# esp32programmer.net
KiCad netlist of a schematic drawn in EAGLE
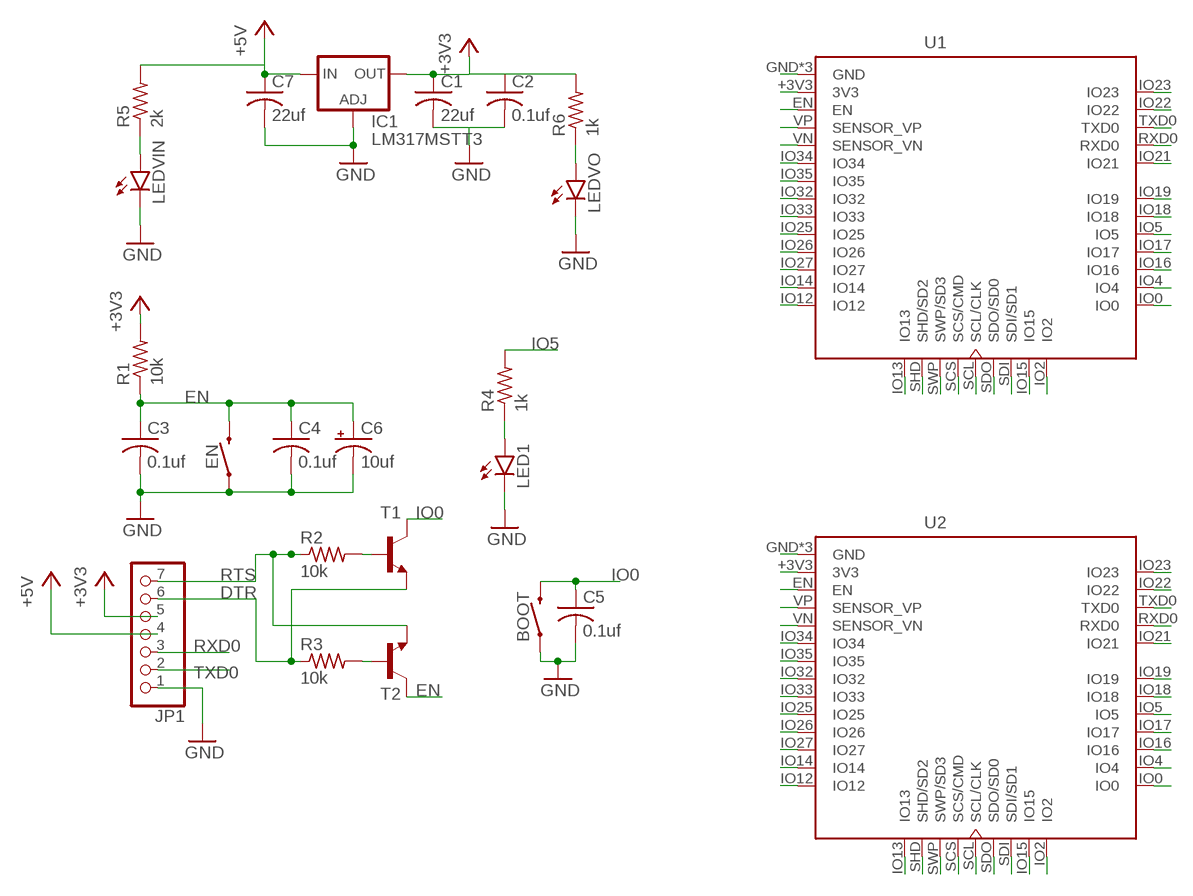
[diagram p0: schematic, sheet 1]

(export (version "E")
  (design (tool "Eeschema 10.0.6"))
  (components
    (comp (ref "BOOT")
      (value "MOMENTARY-SWITCH-SPST-SMD-4.6X2.8MM")
      (footprint "eagle-import:TACTILE_SWITCH_SMD_4.6X2.8MM")
      (libsource (lib "eagle-import") (part "MOMENTARY-SWITCH-SPST-SMD-4.6X2.8MM"))
    )
    (comp (ref "C1")
      (value "22uf")
      (footprint "eagle-import:C1210")
      (libsource (lib "eagle-import") (part "C-USC1210"))
    )
    (comp (ref "C2")
      (value "0.1uf")
      (footprint "eagle-import:C0805")
      (libsource (lib "eagle-import") (part "C-USC0805"))
    )
    (comp (ref "C3")
      (value "0.1uf")
      (footprint "eagle-import:C0805")
      (libsource (lib "eagle-import") (part "C-USC0805"))
    )
    (comp (ref "C4")
      (value "0.1uf")
      (footprint "eagle-import:C0805")
      (libsource (lib "eagle-import") (part "C-USC0805"))
    )
    (comp (ref "C5")
      (value "0.1uf")
      (footprint "eagle-import:C0805")
      (libsource (lib "eagle-import") (part "C-USC0805"))
    )
    (comp (ref "C6")
      (value "10uf")
      (footprint "eagle-import:153CLV-0605")
      (libsource (lib "eagle-import") (part "CPOL-US153CLV-0605"))
    )
    (comp (ref "C7")
      (value "22uf")
      (footprint "eagle-import:C1210")
      (libsource (lib "eagle-import") (part "C-USC1210"))
    )
    (comp (ref "EN")
      (value "MOMENTARY-SWITCH-SPST-SMD-4.6X2.8MM")
      (footprint "eagle-import:TACTILE_SWITCH_SMD_4.6X2.8MM")
      (libsource (lib "eagle-import") (part "MOMENTARY-SWITCH-SPST-SMD-4.6X2.8MM"))
    )
    (comp (ref "IC1")
      (value "LM317MSTT3")
      (footprint "eagle-import:SOT223")
      (libsource (lib "eagle-import") (part "LM317?MSTT3"))
    )
    (comp (ref "JP1")
      (value "PINHD-1X7")
      (footprint "eagle-import:1X07")
      (libsource (lib "eagle-import") (part "PINHD-1X7"))
    )
    (comp (ref "LED1")
      (value "LEDSML0805")
      (footprint "eagle-import:SML0805")
      (libsource (lib "eagle-import") (part "LEDSML0805"))
    )
    (comp (ref "LEDVIN")
      (value "LEDSML0805")
      (footprint "eagle-import:SML0805")
      (libsource (lib "eagle-import") (part "LEDSML0805"))
    )
    (comp (ref "LEDVO")
      (value "LEDSML0805")
      (footprint "eagle-import:SML0805")
      (libsource (lib "eagle-import") (part "LEDSML0805"))
    )
    (comp (ref "R1")
      (value "10k")
      (footprint "eagle-import:R0805")
      (libsource (lib "eagle-import") (part "R-US_R0805"))
    )
    (comp (ref "R2")
      (value "10k")
      (footprint "eagle-import:M0805")
      (libsource (lib "eagle-import") (part "R-US_M0805"))
    )
    (comp (ref "R3")
      (value "10k")
      (footprint "eagle-import:M0805")
      (libsource (lib "eagle-import") (part "R-US_M0805"))
    )
    (comp (ref "R4")
      (value "1k")
      (footprint "eagle-import:R0805")
      (libsource (lib "eagle-import") (part "R-US_R0805"))
    )
    (comp (ref "R5")
      (value "2k")
      (footprint "eagle-import:R0805")
      (libsource (lib "eagle-import") (part "R-US_R0805"))
    )
    (comp (ref "R6")
      (value "1k")
      (footprint "eagle-import:R0805")
      (libsource (lib "eagle-import") (part "R-US_R0805"))
    )
    (comp (ref "T1")
      (value "-NPN-SOT23-EBC")
      (footprint "eagle-import:SOT23-EBC")
      (libsource (lib "eagle-import") (part "-NPN-SOT23-EBC"))
    )
    (comp (ref "T2")
      (value "-NPN-SOT23-EBC")
      (footprint "eagle-import:SOT23-EBC")
      (libsource (lib "eagle-import") (part "-NPN-SOT23-EBC"))
    )
    (comp (ref "U1")
      (value "ESP32-32DADAPTOR")
      (footprint "eagle-import:ESP32_MODULE_ADAPTOR")
      (libsource (lib "eagle-import") (part "ESP32-32DADAPTOR"))
    )
    (comp (ref "U2")
      (value "ESP32-32DADAPTOR")
      (footprint "eagle-import:ESP32_MODULE_ADAPTOR")
      (libsource (lib "eagle-import") (part "ESP32-32DADAPTOR"))
    )
  )
  (nets
    (net (code "1") (name "+3V3") (class "Default")
      (node (ref "C1") (pin "1") (pinfunction "1_1") (pintype "passive"))
      (node (ref "C2") (pin "1") (pinfunction "1_1") (pintype "passive"))
      (node (ref "IC1") (pin "4") (pinfunction "OUT_4") (pintype "passive"))
      (node (ref "JP1") (pin "5") (pinfunction "5_5") (pintype "passive"))
      (node (ref "R1") (pin "2") (pinfunction "2_2") (pintype "passive"))
      (node (ref "R6") (pin "2") (pinfunction "2_2") (pintype "passive"))
      (node (ref "U1") (pin "+3V3") (pinfunction "3V3_+3V3") (pintype "power_in"))
      (node (ref "U2") (pin "+3V3") (pinfunction "3V3_+3V3") (pintype "power_in"))
    )
    (net (code "2") (name "+5V") (class "Default")
      (node (ref "C7") (pin "1") (pinfunction "1_1") (pintype "passive"))
      (node (ref "IC1") (pin "3") (pinfunction "IN_3") (pintype "input"))
      (node (ref "JP1") (pin "4") (pinfunction "4_4") (pintype "passive"))
      (node (ref "R5") (pin "2") (pinfunction "2_2") (pintype "passive"))
    )
    (net (code "3") (name "/DTR") (class "Default")
      (node (ref "JP1") (pin "6") (pinfunction "6_6") (pintype "passive"))
      (node (ref "R3") (pin "1") (pinfunction "1_1") (pintype "passive"))
      (node (ref "T1") (pin "E") (pinfunction "E_E") (pintype "passive"))
    )
    (net (code "4") (name "/EN") (class "Default")
      (node (ref "C3") (pin "1") (pinfunction "1_1") (pintype "passive"))
      (node (ref "C4") (pin "1") (pinfunction "1_1") (pintype "passive"))
      (node (ref "C6") (pin "+") (pinfunction "+_+") (pintype "passive"))
      (node (ref "EN") (pin "3") (pinfunction "2_3") (pintype "passive"))
      (node (ref "EN") (pin "4") (pinfunction "2_4") (pintype "passive"))
      (node (ref "R1") (pin "1") (pinfunction "1_1") (pintype "passive"))
      (node (ref "T2") (pin "C") (pinfunction "C_C") (pintype "passive"))
      (node (ref "U1") (pin "EN") (pinfunction "EN_EN") (pintype "input"))
      (node (ref "U2") (pin "EN") (pinfunction "EN_EN") (pintype "input"))
    )
    (net (code "5") (name "/IO0") (class "Default")
      (node (ref "BOOT") (pin "3") (pinfunction "2_3") (pintype "passive"))
      (node (ref "BOOT") (pin "4") (pinfunction "2_4") (pintype "passive"))
      (node (ref "C5") (pin "1") (pinfunction "1_1") (pintype "passive"))
      (node (ref "T1") (pin "C") (pinfunction "C_C") (pintype "passive"))
      (node (ref "U1") (pin "IO0") (pinfunction "IO0_IO0") (pintype "bidirectional"))
      (node (ref "U2") (pin "IO0") (pinfunction "IO0_IO0") (pintype "bidirectional"))
    )
    (net (code "6") (name "/IO2") (class "Default")
      (node (ref "U1") (pin "IO2") (pinfunction "IO2_IO2") (pintype "bidirectional"))
      (node (ref "U2") (pin "IO2") (pinfunction "IO2_IO2") (pintype "bidirectional"))
    )
    (net (code "7") (name "/IO4") (class "Default")
      (node (ref "U1") (pin "IO4") (pinfunction "IO4_IO4") (pintype "bidirectional"))
      (node (ref "U2") (pin "IO4") (pinfunction "IO4_IO4") (pintype "bidirectional"))
    )
    (net (code "8") (name "/IO5") (class "Default")
      (node (ref "R4") (pin "2") (pinfunction "2_2") (pintype "passive"))
      (node (ref "U1") (pin "IO5") (pinfunction "IO5_IO5") (pintype "bidirectional"))
      (node (ref "U2") (pin "IO5") (pinfunction "IO5_IO5") (pintype "bidirectional"))
    )
    (net (code "9") (name "/IO12") (class "Default")
      (node (ref "U1") (pin "IO12") (pinfunction "IO12_IO12") (pintype "bidirectional"))
      (node (ref "U2") (pin "IO12") (pinfunction "IO12_IO12") (pintype "bidirectional"))
    )
    (net (code "10") (name "/IO13") (class "Default")
      (node (ref "U1") (pin "IO13") (pinfunction "IO13_IO13") (pintype "bidirectional"))
      (node (ref "U2") (pin "IO13") (pinfunction "IO13_IO13") (pintype "bidirectional"))
    )
    (net (code "11") (name "/IO14") (class "Default")
      (node (ref "U1") (pin "IO14") (pinfunction "IO14_IO14") (pintype "bidirectional"))
      (node (ref "U2") (pin "IO14") (pinfunction "IO14_IO14") (pintype "bidirectional"))
    )
    (net (code "12") (name "/IO15") (class "Default")
      (node (ref "U1") (pin "IO15") (pinfunction "IO15_IO15") (pintype "bidirectional"))
      (node (ref "U2") (pin "IO15") (pinfunction "IO15_IO15") (pintype "bidirectional"))
    )
    (net (code "13") (name "/IO16") (class "Default")
      (node (ref "U1") (pin "IO16") (pinfunction "IO16_IO16") (pintype "bidirectional"))
      (node (ref "U2") (pin "IO16") (pinfunction "IO16_IO16") (pintype "bidirectional"))
    )
    (net (code "14") (name "/IO17") (class "Default")
      (node (ref "U1") (pin "IO17") (pinfunction "IO17_IO17") (pintype "bidirectional"))
      (node (ref "U2") (pin "IO17") (pinfunction "IO17_IO17") (pintype "bidirectional"))
    )
    (net (code "15") (name "/IO18") (class "Default")
      (node (ref "U1") (pin "IO18") (pinfunction "IO18_IO18") (pintype "bidirectional"))
      (node (ref "U2") (pin "IO18") (pinfunction "IO18_IO18") (pintype "bidirectional"))
    )
    (net (code "16") (name "/IO19") (class "Default")
      (node (ref "U1") (pin "IO19") (pinfunction "IO19_IO19") (pintype "bidirectional"))
      (node (ref "U2") (pin "IO19") (pinfunction "IO19_IO19") (pintype "bidirectional"))
    )
    (net (code "17") (name "/IO21") (class "Default")
      (node (ref "U1") (pin "IO21") (pinfunction "IO21_IO21") (pintype "bidirectional"))
      (node (ref "U2") (pin "IO21") (pinfunction "IO21_IO21") (pintype "bidirectional"))
    )
    (net (code "18") (name "/IO22") (class "Default")
      (node (ref "U1") (pin "IO22") (pinfunction "IO22_IO22") (pintype "bidirectional"))
      (node (ref "U2") (pin "IO22") (pinfunction "IO22_IO22") (pintype "bidirectional"))
    )
    (net (code "19") (name "/IO23") (class "Default")
      (node (ref "U1") (pin "IO23") (pinfunction "IO23_IO23") (pintype "bidirectional"))
      (node (ref "U2") (pin "IO23") (pinfunction "IO23_IO23") (pintype "bidirectional"))
    )
    (net (code "20") (name "/IO25") (class "Default")
      (node (ref "U1") (pin "IO25") (pinfunction "IO25_IO25") (pintype "bidirectional"))
      (node (ref "U2") (pin "IO25") (pinfunction "IO25_IO25") (pintype "bidirectional"))
    )
    (net (code "21") (name "/IO26") (class "Default")
      (node (ref "U1") (pin "IO26") (pinfunction "IO26_IO26") (pintype "bidirectional"))
      (node (ref "U2") (pin "IO26") (pinfunction "IO26_IO26") (pintype "bidirectional"))
    )
    (net (code "22") (name "/IO27") (class "Default")
      (node (ref "U1") (pin "IO27") (pinfunction "IO27_IO27") (pintype "bidirectional"))
      (node (ref "U2") (pin "IO27") (pinfunction "IO27_IO27") (pintype "bidirectional"))
    )
    (net (code "23") (name "/IO32") (class "Default")
      (node (ref "U1") (pin "IO32") (pinfunction "IO32_IO32") (pintype "bidirectional"))
      (node (ref "U2") (pin "IO32") (pinfunction "IO32_IO32") (pintype "bidirectional"))
    )
    (net (code "24") (name "/IO33") (class "Default")
      (node (ref "U1") (pin "IO33") (pinfunction "IO33_IO33") (pintype "bidirectional"))
      (node (ref "U2") (pin "IO33") (pinfunction "IO33_IO33") (pintype "bidirectional"))
    )
    (net (code "25") (name "/IO34") (class "Default")
      (node (ref "U1") (pin "IO34") (pinfunction "IO34_IO34") (pintype "bidirectional"))
      (node (ref "U2") (pin "IO34") (pinfunction "IO34_IO34") (pintype "bidirectional"))
    )
    (net (code "26") (name "/IO35") (class "Default")
      (node (ref "U1") (pin "IO35") (pinfunction "IO35_IO35") (pintype "bidirectional"))
      (node (ref "U2") (pin "IO35") (pinfunction "IO35_IO35") (pintype "bidirectional"))
    )
    (net (code "27") (name "/RTS") (class "Default")
      (node (ref "JP1") (pin "7") (pinfunction "7_7") (pintype "passive"))
      (node (ref "R2") (pin "1") (pinfunction "1_1") (pintype "passive"))
      (node (ref "T2") (pin "E") (pinfunction "E_E") (pintype "passive"))
    )
    (net (code "28") (name "/RXD0") (class "Default")
      (node (ref "JP1") (pin "3") (pinfunction "3_3") (pintype "passive"))
      (node (ref "U1") (pin "RXD0") (pinfunction "RXD0_RXD0") (pintype "bidirectional"))
      (node (ref "U2") (pin "RXD0") (pinfunction "RXD0_RXD0") (pintype "bidirectional"))
    )
    (net (code "29") (name "/SCL") (class "Default")
      (node (ref "U1") (pin "SCL") (pinfunction "SCL/CLK_SCL") (pintype "bidirectional"))
      (node (ref "U2") (pin "SCL") (pinfunction "SCL/CLK_SCL") (pintype "bidirectional"))
    )
    (net (code "30") (name "/SCS") (class "Default")
      (node (ref "U1") (pin "SCS") (pinfunction "SCS/CMD_SCS") (pintype "bidirectional"))
      (node (ref "U2") (pin "SCS") (pinfunction "SCS/CMD_SCS") (pintype "bidirectional"))
    )
    (net (code "31") (name "/SDI") (class "Default")
      (node (ref "U1") (pin "SDI") (pinfunction "SDI/SD1_SDI") (pintype "bidirectional"))
      (node (ref "U2") (pin "SDI") (pinfunction "SDI/SD1_SDI") (pintype "bidirectional"))
    )
    (net (code "32") (name "/SDO") (class "Default")
      (node (ref "U1") (pin "SDO") (pinfunction "SDO/SD0_SDO") (pintype "bidirectional"))
      (node (ref "U2") (pin "SDO") (pinfunction "SDO/SD0_SDO") (pintype "bidirectional"))
    )
    (net (code "33") (name "/SHD") (class "Default")
      (node (ref "U1") (pin "SHD") (pinfunction "SHD/SD2_SHD") (pintype "bidirectional"))
      (node (ref "U2") (pin "SHD") (pinfunction "SHD/SD2_SHD") (pintype "bidirectional"))
    )
    (net (code "34") (name "/SWP") (class "Default")
      (node (ref "U1") (pin "SWP") (pinfunction "SWP/SD3_SWP") (pintype "bidirectional"))
      (node (ref "U2") (pin "SWP") (pinfunction "SWP/SD3_SWP") (pintype "bidirectional"))
    )
    (net (code "35") (name "/TXD0") (class "Default")
      (node (ref "JP1") (pin "2") (pinfunction "2_2") (pintype "passive"))
      (node (ref "U1") (pin "TXD0") (pinfunction "TXD0_TXD0") (pintype "bidirectional"))
      (node (ref "U2") (pin "TXD0") (pinfunction "TXD0_TXD0") (pintype "bidirectional"))
    )
    (net (code "36") (name "/VN") (class "Default")
      (node (ref "U1") (pin "VN") (pinfunction "SENSOR_VN_VN") (pintype "input"))
      (node (ref "U2") (pin "VN") (pinfunction "SENSOR_VN_VN") (pintype "input"))
    )
    (net (code "37") (name "/VP") (class "Default")
      (node (ref "U1") (pin "VP") (pinfunction "SENSOR_VP_VP") (pintype "input"))
      (node (ref "U2") (pin "VP") (pinfunction "SENSOR_VP_VP") (pintype "input"))
    )
    (net (code "38") (name "GND") (class "Default")
      (node (ref "BOOT") (pin "1") (pinfunction "1_1") (pintype "passive"))
      (node (ref "BOOT") (pin "2") (pinfunction "1_2") (pintype "passive"))
      (node (ref "C1") (pin "2") (pinfunction "2_2") (pintype "passive"))
      (node (ref "C2") (pin "2") (pinfunction "2_2") (pintype "passive"))
      (node (ref "C3") (pin "2") (pinfunction "2_2") (pintype "passive"))
      (node (ref "C4") (pin "2") (pinfunction "2_2") (pintype "passive"))
      (node (ref "C5") (pin "2") (pinfunction "2_2") (pintype "passive"))
      (node (ref "C6") (pin "-") (pinfunction "-_-") (pintype "passive"))
      (node (ref "C7") (pin "2") (pinfunction "2_2") (pintype "passive"))
      (node (ref "EN") (pin "1") (pinfunction "1_1") (pintype "passive"))
      (node (ref "EN") (pin "2") (pinfunction "1_2") (pintype "passive"))
      (node (ref "IC1") (pin "1") (pinfunction "ADJ_1") (pintype "input"))
      (node (ref "JP1") (pin "1") (pinfunction "1_1") (pintype "passive"))
      (node (ref "LED1") (pin "C") (pinfunction "C_C") (pintype "passive"))
      (node (ref "LEDVIN") (pin "C") (pinfunction "C_C") (pintype "passive"))
      (node (ref "LEDVO") (pin "C") (pinfunction "C_C") (pintype "passive"))
      (node (ref "U1") (pin "GND") (pinfunction "GND_GND") (pintype "power_in"))
      (node (ref "U1") (pin "GND@1") (pinfunction "GND_GND@1") (pintype "power_in"))
      (node (ref "U1") (pin "GND@3") (pinfunction "GND_GND@3") (pintype "power_in"))
      (node (ref "U2") (pin "GND") (pinfunction "GND_GND") (pintype "power_in"))
      (node (ref "U2") (pin "GND@1") (pinfunction "GND_GND@1") (pintype "power_in"))
      (node (ref "U2") (pin "GND@3") (pinfunction "GND_GND@3") (pintype "power_in"))
    )
    (net (code "39") (name "Net-(LED1-PadA)") (class "Default")
      (node (ref "LED1") (pin "A") (pinfunction "A_A") (pintype "passive"))
      (node (ref "R4") (pin "1") (pinfunction "1_1") (pintype "passive"))
    )
    (net (code "40") (name "Net-(LEDVIN-PadA)") (class "Default")
      (node (ref "LEDVIN") (pin "A") (pinfunction "A_A") (pintype "passive"))
      (node (ref "R5") (pin "1") (pinfunction "1_1") (pintype "passive"))
    )
    (net (code "41") (name "Net-(LEDVO-PadA)") (class "Default")
      (node (ref "LEDVO") (pin "A") (pinfunction "A_A") (pintype "passive"))
      (node (ref "R6") (pin "1") (pinfunction "1_1") (pintype "passive"))
    )
    (net (code "42") (name "Net-(R2-Pad2)") (class "Default")
      (node (ref "R2") (pin "2") (pinfunction "2_2") (pintype "passive"))
      (node (ref "T1") (pin "B") (pinfunction "B_B") (pintype "passive"))
    )
    (net (code "43") (name "Net-(R3-Pad2)") (class "Default")
      (node (ref "R3") (pin "2") (pinfunction "2_2") (pintype "passive"))
      (node (ref "T2") (pin "B") (pinfunction "B_B") (pintype "passive"))
    )
  )
)
